# slave-V11.net
KiCad netlist of a schematic drawn in EAGLE
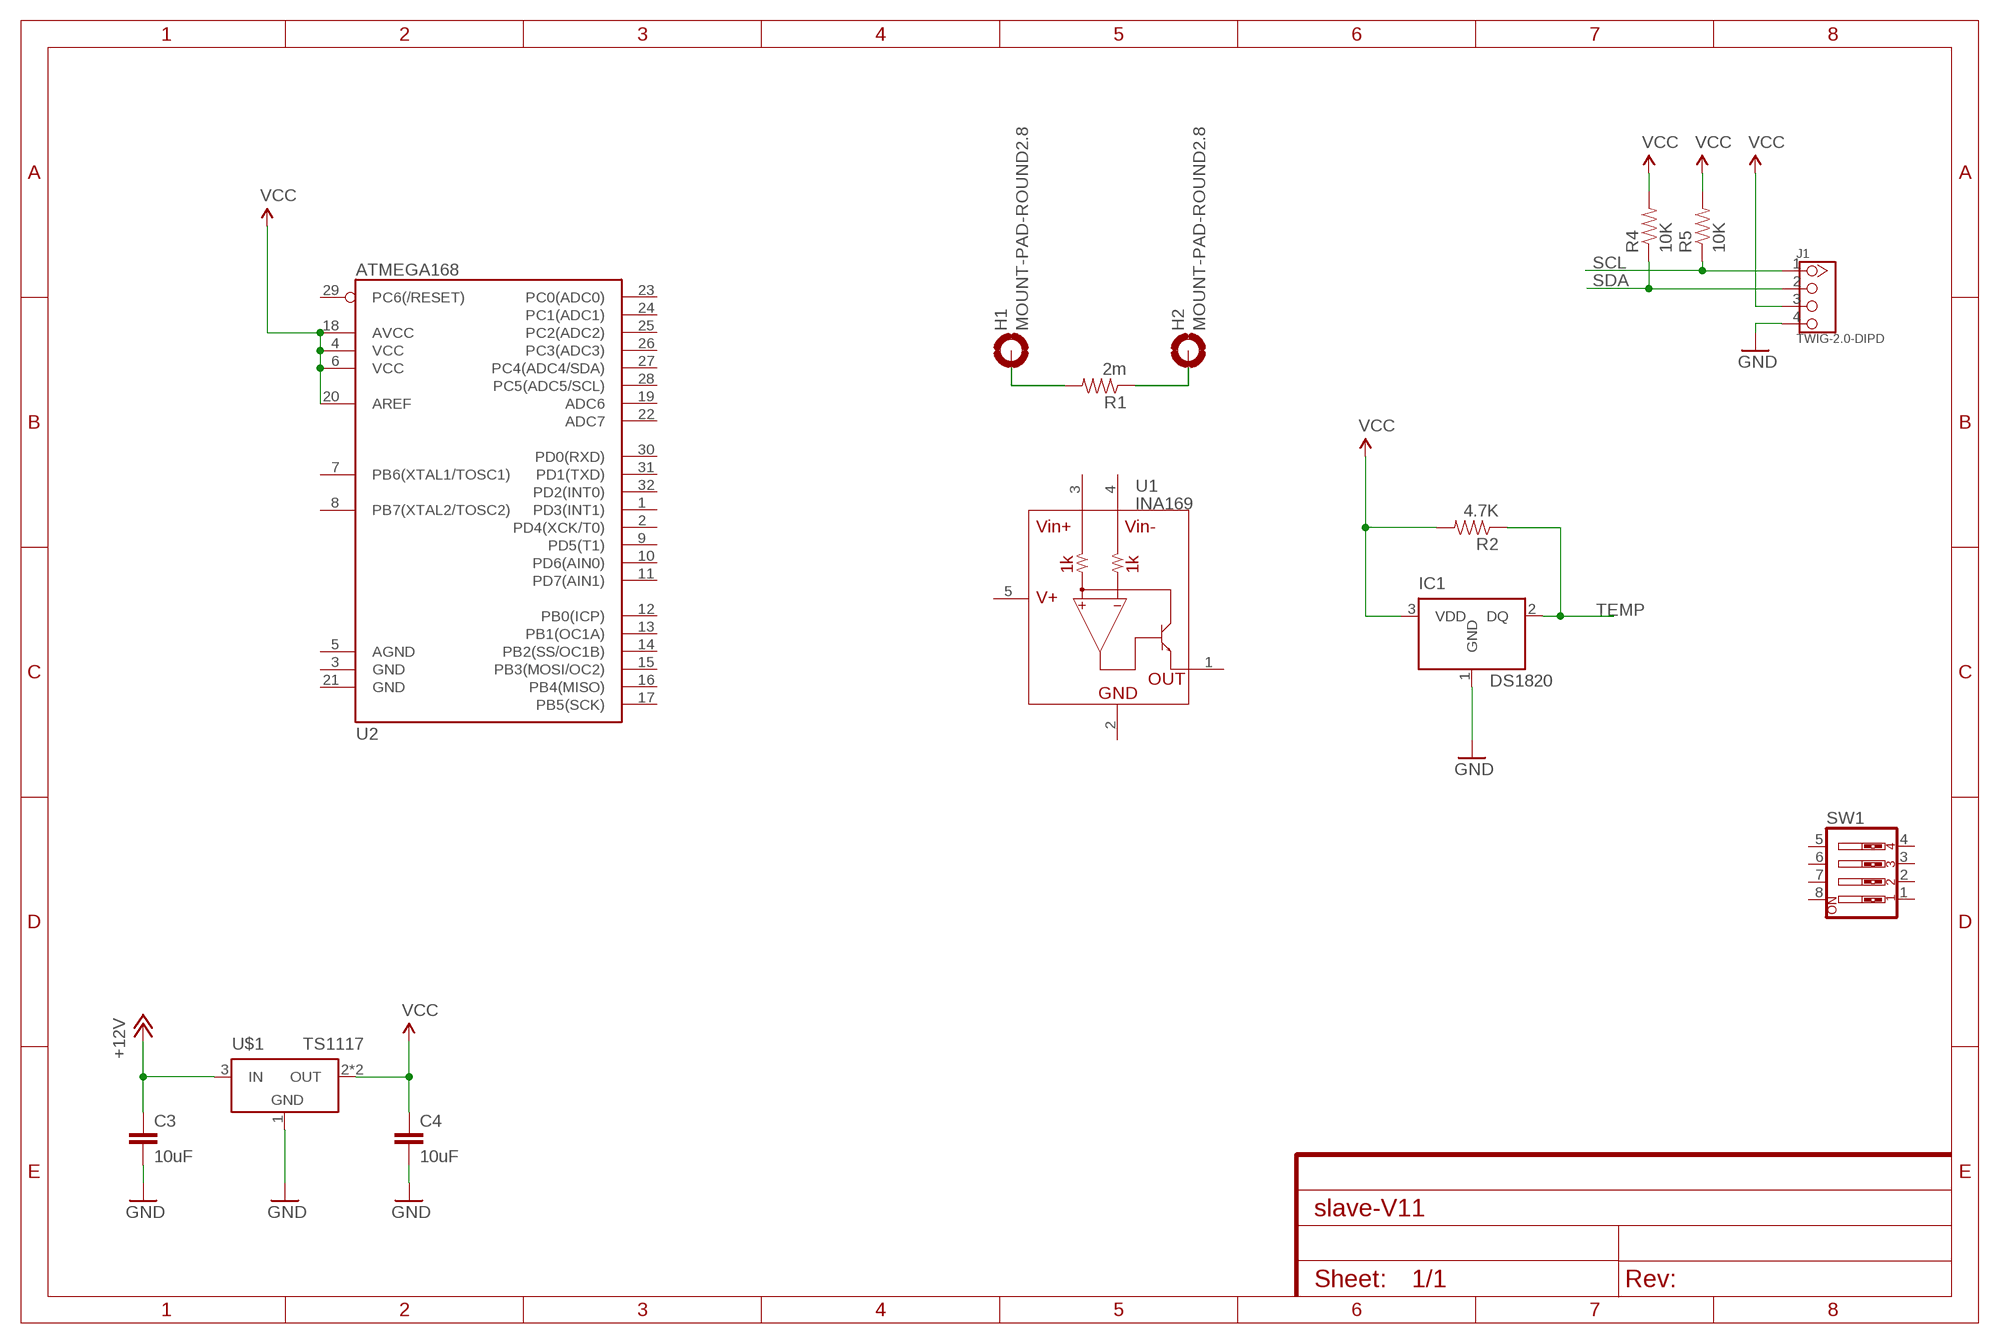
[diagram p0: schematic, sheet 1]

(export (version "E")
  (design (tool "Eeschema 10.0.6"))
  (components
    (comp (ref "C3")
      (value "10uF")
      (footprint "eagle-import:0805")
      (libsource (lib "eagle-import") (part "CAP0805"))
    )
    (comp (ref "C4")
      (value "10uF")
      (footprint "eagle-import:0805")
      (libsource (lib "eagle-import") (part "CAP0805"))
    )
    (comp (ref "H1")
      (value "MOUNT-PAD-ROUND2.8")
      (footprint "eagle-import:2,8-PAD")
      (libsource (lib "eagle-import") (part "MOUNT-PAD-ROUND2.8"))
    )
    (comp (ref "H2")
      (value "MOUNT-PAD-ROUND2.8")
      (footprint "eagle-import:2,8-PAD")
      (libsource (lib "eagle-import") (part "MOUNT-PAD-ROUND2.8"))
    )
    (comp (ref "IC1")
      (value "DS1820")
      (footprint "eagle-import:TO-92")
      (libsource (lib "eagle-import") (part "DS1820"))
    )
    (comp (ref "J1")
      (value "TWIG-2.0-DIPD")
      (footprint "eagle-import:2.0_1X4_90")
      (libsource (lib "eagle-import") (part "TWIG-2.0-DIPD"))
    )
    (comp (ref "R1")
      (value "2m")
      (footprint "eagle-import:R2512")
      (libsource (lib "eagle-import") (part "RESISTOR2512"))
    )
    (comp (ref "R2")
      (value "4.7K")
      (footprint "eagle-import:0805")
      (libsource (lib "eagle-import") (part "RESISTOR0805-RES"))
    )
    (comp (ref "R4")
      (value "10K")
      (footprint "eagle-import:0805")
      (libsource (lib "eagle-import") (part "RESISTOR0805-RES"))
    )
    (comp (ref "R5")
      (value "10K")
      (footprint "eagle-import:0805")
      (libsource (lib "eagle-import") (part "RESISTOR0805-RES"))
    )
    (comp (ref "SW1")
      (value "SW_DIP-4")
      (footprint "eagle-import:EDG-04")
      (libsource (lib "eagle-import") (part "SW_DIP-4"))
    )
    (comp (ref "U$1")
      (value "TS1117")
      (footprint "eagle-import:SOT223")
      (libsource (lib "eagle-import") (part "TS1117"))
    )
    (comp (ref "U1")
      (value "INA169")
      (footprint "eagle-import:SOT23-5")
      (libsource (lib "eagle-import") (part "INA169"))
    )
    (comp (ref "U2")
      (value "ATMEGA168")
      (footprint "eagle-import:TQFP32-08")
      (libsource (lib "eagle-import") (part "ATMEGA168"))
    )
  )
  (nets
    (net (code "1") (name "+12V") (class "Default")
      (node (ref "C3") (pin "1") (pinfunction "1_1") (pintype "passive"))
      (node (ref "U$1") (pin "3") (pinfunction "IN_3") (pintype "input"))
    )
    (net (code "2") (name "/SCL") (class "Default")
      (node (ref "J1") (pin "1") (pinfunction "1_1") (pintype "bidirectional"))
      (node (ref "R5") (pin "1") (pinfunction "1_1") (pintype "passive"))
    )
    (net (code "3") (name "/SDA") (class "Default")
      (node (ref "J1") (pin "2") (pinfunction "2_2") (pintype "bidirectional"))
      (node (ref "R4") (pin "1") (pinfunction "1_1") (pintype "passive"))
    )
    (net (code "4") (name "/TEMP") (class "Default")
      (node (ref "IC1") (pin "2") (pinfunction "DQ_2") (pintype "output"))
      (node (ref "R2") (pin "1") (pinfunction "1_1") (pintype "passive"))
    )
    (net (code "5") (name "GND") (class "Default")
      (node (ref "C3") (pin "2") (pinfunction "2_2") (pintype "passive"))
      (node (ref "C4") (pin "2") (pinfunction "2_2") (pintype "passive"))
      (node (ref "IC1") (pin "1") (pinfunction "GND_1") (pintype "power_in"))
      (node (ref "J1") (pin "4") (pinfunction "4_4") (pintype "bidirectional"))
      (node (ref "U$1") (pin "1") (pinfunction "GND_1") (pintype "power_in"))
    )
    (net (code "6") (name "Net-(H1-MOUNT)") (class "Default")
      (node (ref "H1") (pin "B2,8") (pinfunction "MOUNT_B2,8") (pintype "passive"))
      (node (ref "R1") (pin "2") (pinfunction "2_2") (pintype "passive"))
    )
    (net (code "7") (name "Net-(H2-MOUNT)") (class "Default")
      (node (ref "H2") (pin "B2,8") (pinfunction "MOUNT_B2,8") (pintype "passive"))
      (node (ref "R1") (pin "1") (pinfunction "1_1") (pintype "passive"))
    )
    (net (code "8") (name "VCC") (class "Default")
      (node (ref "C4") (pin "1") (pinfunction "1_1") (pintype "passive"))
      (node (ref "IC1") (pin "3") (pinfunction "VDD_3") (pintype "input"))
      (node (ref "J1") (pin "3") (pinfunction "3_3") (pintype "bidirectional"))
      (node (ref "R2") (pin "2") (pinfunction "2_2") (pintype "passive"))
      (node (ref "R4") (pin "2") (pinfunction "2_2") (pintype "passive"))
      (node (ref "R5") (pin "2") (pinfunction "2_2") (pintype "passive"))
      (node (ref "U$1") (pin "2") (pinfunction "OUT_2") (pintype "output"))
      (node (ref "U$1") (pin "4") (pinfunction "OUT_4") (pintype "output"))
      (node (ref "U2") (pin "18") (pinfunction "AVCC_18") (pintype "bidirectional"))
      (node (ref "U2") (pin "20") (pinfunction "AREF_20") (pintype "bidirectional"))
      (node (ref "U2") (pin "4") (pinfunction "VCC_4") (pintype "bidirectional"))
      (node (ref "U2") (pin "6") (pinfunction "VCC_6") (pintype "bidirectional"))
    )
    (net (code "9") (name "unconnected-(SW1-Pad1)") (class "Default")
      (node (ref "SW1") (pin "1") (pinfunction "1_1") (pintype "passive"))
    )
    (net (code "10") (name "unconnected-(SW1-Pad2)") (class "Default")
      (node (ref "SW1") (pin "2") (pinfunction "2_2") (pintype "passive"))
    )
    (net (code "11") (name "unconnected-(SW1-Pad3)") (class "Default")
      (node (ref "SW1") (pin "3") (pinfunction "3_3") (pintype "passive"))
    )
    (net (code "12") (name "unconnected-(SW1-Pad4)") (class "Default")
      (node (ref "SW1") (pin "4") (pinfunction "4_4") (pintype "passive"))
    )
    (net (code "13") (name "unconnected-(SW1-Pad5)") (class "Default")
      (node (ref "SW1") (pin "5") (pinfunction "5_5") (pintype "passive"))
    )
    (net (code "14") (name "unconnected-(SW1-Pad6)") (class "Default")
      (node (ref "SW1") (pin "6") (pinfunction "6_6") (pintype "passive"))
    )
    (net (code "15") (name "unconnected-(SW1-Pad7)") (class "Default")
      (node (ref "SW1") (pin "7") (pinfunction "7_7") (pintype "passive"))
    )
    (net (code "16") (name "unconnected-(SW1-Pad8)") (class "Default")
      (node (ref "SW1") (pin "8") (pinfunction "8_8") (pintype "passive"))
    )
    (net (code "17") (name "unconnected-(U1-GND-Pad2)") (class "Default")
      (node (ref "U1") (pin "2") (pinfunction "GND_2") (pintype "bidirectional"))
    )
    (net (code "18") (name "unconnected-(U1-OUT-Pad1)") (class "Default")
      (node (ref "U1") (pin "1") (pinfunction "OUT_1") (pintype "bidirectional"))
    )
    (net (code "19") (name "unconnected-(U1-V+-Pad5)") (class "Default")
      (node (ref "U1") (pin "5") (pinfunction "V+_5") (pintype "bidirectional"))
    )
    (net (code "20") (name "unconnected-(U1-VIN+-Pad3)") (class "Default")
      (node (ref "U1") (pin "3") (pinfunction "VIN+_3") (pintype "bidirectional"))
    )
    (net (code "21") (name "unconnected-(U1-VIN--Pad4)") (class "Default")
      (node (ref "U1") (pin "4") (pinfunction "VIN-_4") (pintype "bidirectional"))
    )
    (net (code "22") (name "unconnected-(U2-ADC6-Pad19)") (class "Default")
      (node (ref "U2") (pin "19") (pinfunction "ADC6_19") (pintype "bidirectional"))
    )
    (net (code "23") (name "unconnected-(U2-ADC7-Pad22)") (class "Default")
      (node (ref "U2") (pin "22") (pinfunction "ADC7_22") (pintype "bidirectional"))
    )
    (net (code "24") (name "unconnected-(U2-AGND-Pad5)") (class "Default")
      (node (ref "U2") (pin "5") (pinfunction "AGND_5") (pintype "bidirectional"))
    )
    (net (code "25") (name "unconnected-(U2-GND-Pad3)") (class "Default")
      (node (ref "U2") (pin "3") (pinfunction "GND_3") (pintype "bidirectional"))
    )
    (net (code "26") (name "unconnected-(U2-GND-Pad21)") (class "Default")
      (node (ref "U2") (pin "21") (pinfunction "GND_21") (pintype "bidirectional"))
    )
    (net (code "27") (name "unconnected-(U2-PB0(ICP)-Pad12)") (class "Default")
      (node (ref "U2") (pin "12") (pinfunction "PB0(ICP)_12") (pintype "bidirectional"))
    )
    (net (code "28") (name "unconnected-(U2-PB1(OC1A)-Pad13)") (class "Default")
      (node (ref "U2") (pin "13") (pinfunction "PB1(OC1A)_13") (pintype "bidirectional"))
    )
    (net (code "29") (name "unconnected-(U2-PB2(SS{slash}OC1B)-Pad14)") (class "Default")
      (node (ref "U2") (pin "14") (pinfunction "PB2(SS/OC1B)_14") (pintype "bidirectional"))
    )
    (net (code "30") (name "unconnected-(U2-PB3(MOSI{slash}OC2)-Pad15)") (class "Default")
      (node (ref "U2") (pin "15") (pinfunction "PB3(MOSI/OC2)_15") (pintype "bidirectional"))
    )
    (net (code "31") (name "unconnected-(U2-PB4(MISO)-Pad16)") (class "Default")
      (node (ref "U2") (pin "16") (pinfunction "PB4(MISO)_16") (pintype "bidirectional"))
    )
    (net (code "32") (name "unconnected-(U2-PB5(SCK)-Pad17)") (class "Default")
      (node (ref "U2") (pin "17") (pinfunction "PB5(SCK)_17") (pintype "bidirectional"))
    )
    (net (code "33") (name "unconnected-(U2-PB6(XTAL1{slash}TOSC1)-Pad7)") (class "Default")
      (node (ref "U2") (pin "7") (pinfunction "PB6(XTAL1/TOSC1)_7") (pintype "bidirectional"))
    )
    (net (code "34") (name "unconnected-(U2-PB7(XTAL2{slash}TOSC2)-Pad8)") (class "Default")
      (node (ref "U2") (pin "8") (pinfunction "PB7(XTAL2/TOSC2)_8") (pintype "bidirectional"))
    )
    (net (code "35") (name "unconnected-(U2-PC0(ADC0)-Pad23)") (class "Default")
      (node (ref "U2") (pin "23") (pinfunction "PC0(ADC0)_23") (pintype "bidirectional"))
    )
    (net (code "36") (name "unconnected-(U2-PC1(ADC1)-Pad24)") (class "Default")
      (node (ref "U2") (pin "24") (pinfunction "PC1(ADC1)_24") (pintype "bidirectional"))
    )
    (net (code "37") (name "unconnected-(U2-PC2(ADC2)-Pad25)") (class "Default")
      (node (ref "U2") (pin "25") (pinfunction "PC2(ADC2)_25") (pintype "bidirectional"))
    )
    (net (code "38") (name "unconnected-(U2-PC3(ADC3)-Pad26)") (class "Default")
      (node (ref "U2") (pin "26") (pinfunction "PC3(ADC3)_26") (pintype "bidirectional"))
    )
    (net (code "39") (name "unconnected-(U2-PC4(ADC4{slash}SDA)-Pad27)") (class "Default")
      (node (ref "U2") (pin "27") (pinfunction "PC4(ADC4/SDA)_27") (pintype "bidirectional"))
    )
    (net (code "40") (name "unconnected-(U2-PC5(ADC5{slash}SCL)-Pad28)") (class "Default")
      (node (ref "U2") (pin "28") (pinfunction "PC5(ADC5/SCL)_28") (pintype "bidirectional"))
    )
    (net (code "41") (name "unconnected-(U2-PC6({slash}RESET)-Pad29)") (class "Default")
      (node (ref "U2") (pin "29") (pinfunction "PC6(/RESET)_29") (pintype "bidirectional"))
    )
    (net (code "42") (name "unconnected-(U2-PD0(RXD)-Pad30)") (class "Default")
      (node (ref "U2") (pin "30") (pinfunction "PD0(RXD)_30") (pintype "bidirectional"))
    )
    (net (code "43") (name "unconnected-(U2-PD1(TXD)-Pad31)") (class "Default")
      (node (ref "U2") (pin "31") (pinfunction "PD1(TXD)_31") (pintype "bidirectional"))
    )
    (net (code "44") (name "unconnected-(U2-PD2(INT0)-Pad32)") (class "Default")
      (node (ref "U2") (pin "32") (pinfunction "PD2(INT0)_32") (pintype "bidirectional"))
    )
    (net (code "45") (name "unconnected-(U2-PD3(INT1)-Pad1)") (class "Default")
      (node (ref "U2") (pin "1") (pinfunction "PD3(INT1)_1") (pintype "bidirectional"))
    )
    (net (code "46") (name "unconnected-(U2-PD4(XCK{slash}T0)-Pad2)") (class "Default")
      (node (ref "U2") (pin "2") (pinfunction "PD4(XCK/T0)_2") (pintype "bidirectional"))
    )
    (net (code "47") (name "unconnected-(U2-PD5(T1)-Pad9)") (class "Default")
      (node (ref "U2") (pin "9") (pinfunction "PD5(T1)_9") (pintype "bidirectional"))
    )
    (net (code "48") (name "unconnected-(U2-PD6(AIN0)-Pad10)") (class "Default")
      (node (ref "U2") (pin "10") (pinfunction "PD6(AIN0)_10") (pintype "bidirectional"))
    )
    (net (code "49") (name "unconnected-(U2-PD7(AIN1)-Pad11)") (class "Default")
      (node (ref "U2") (pin "11") (pinfunction "PD7(AIN1)_11") (pintype "bidirectional"))
    )
  )
)
